# Sheet1.net
KiCad netlist of a schematic drawn in Altium Designer
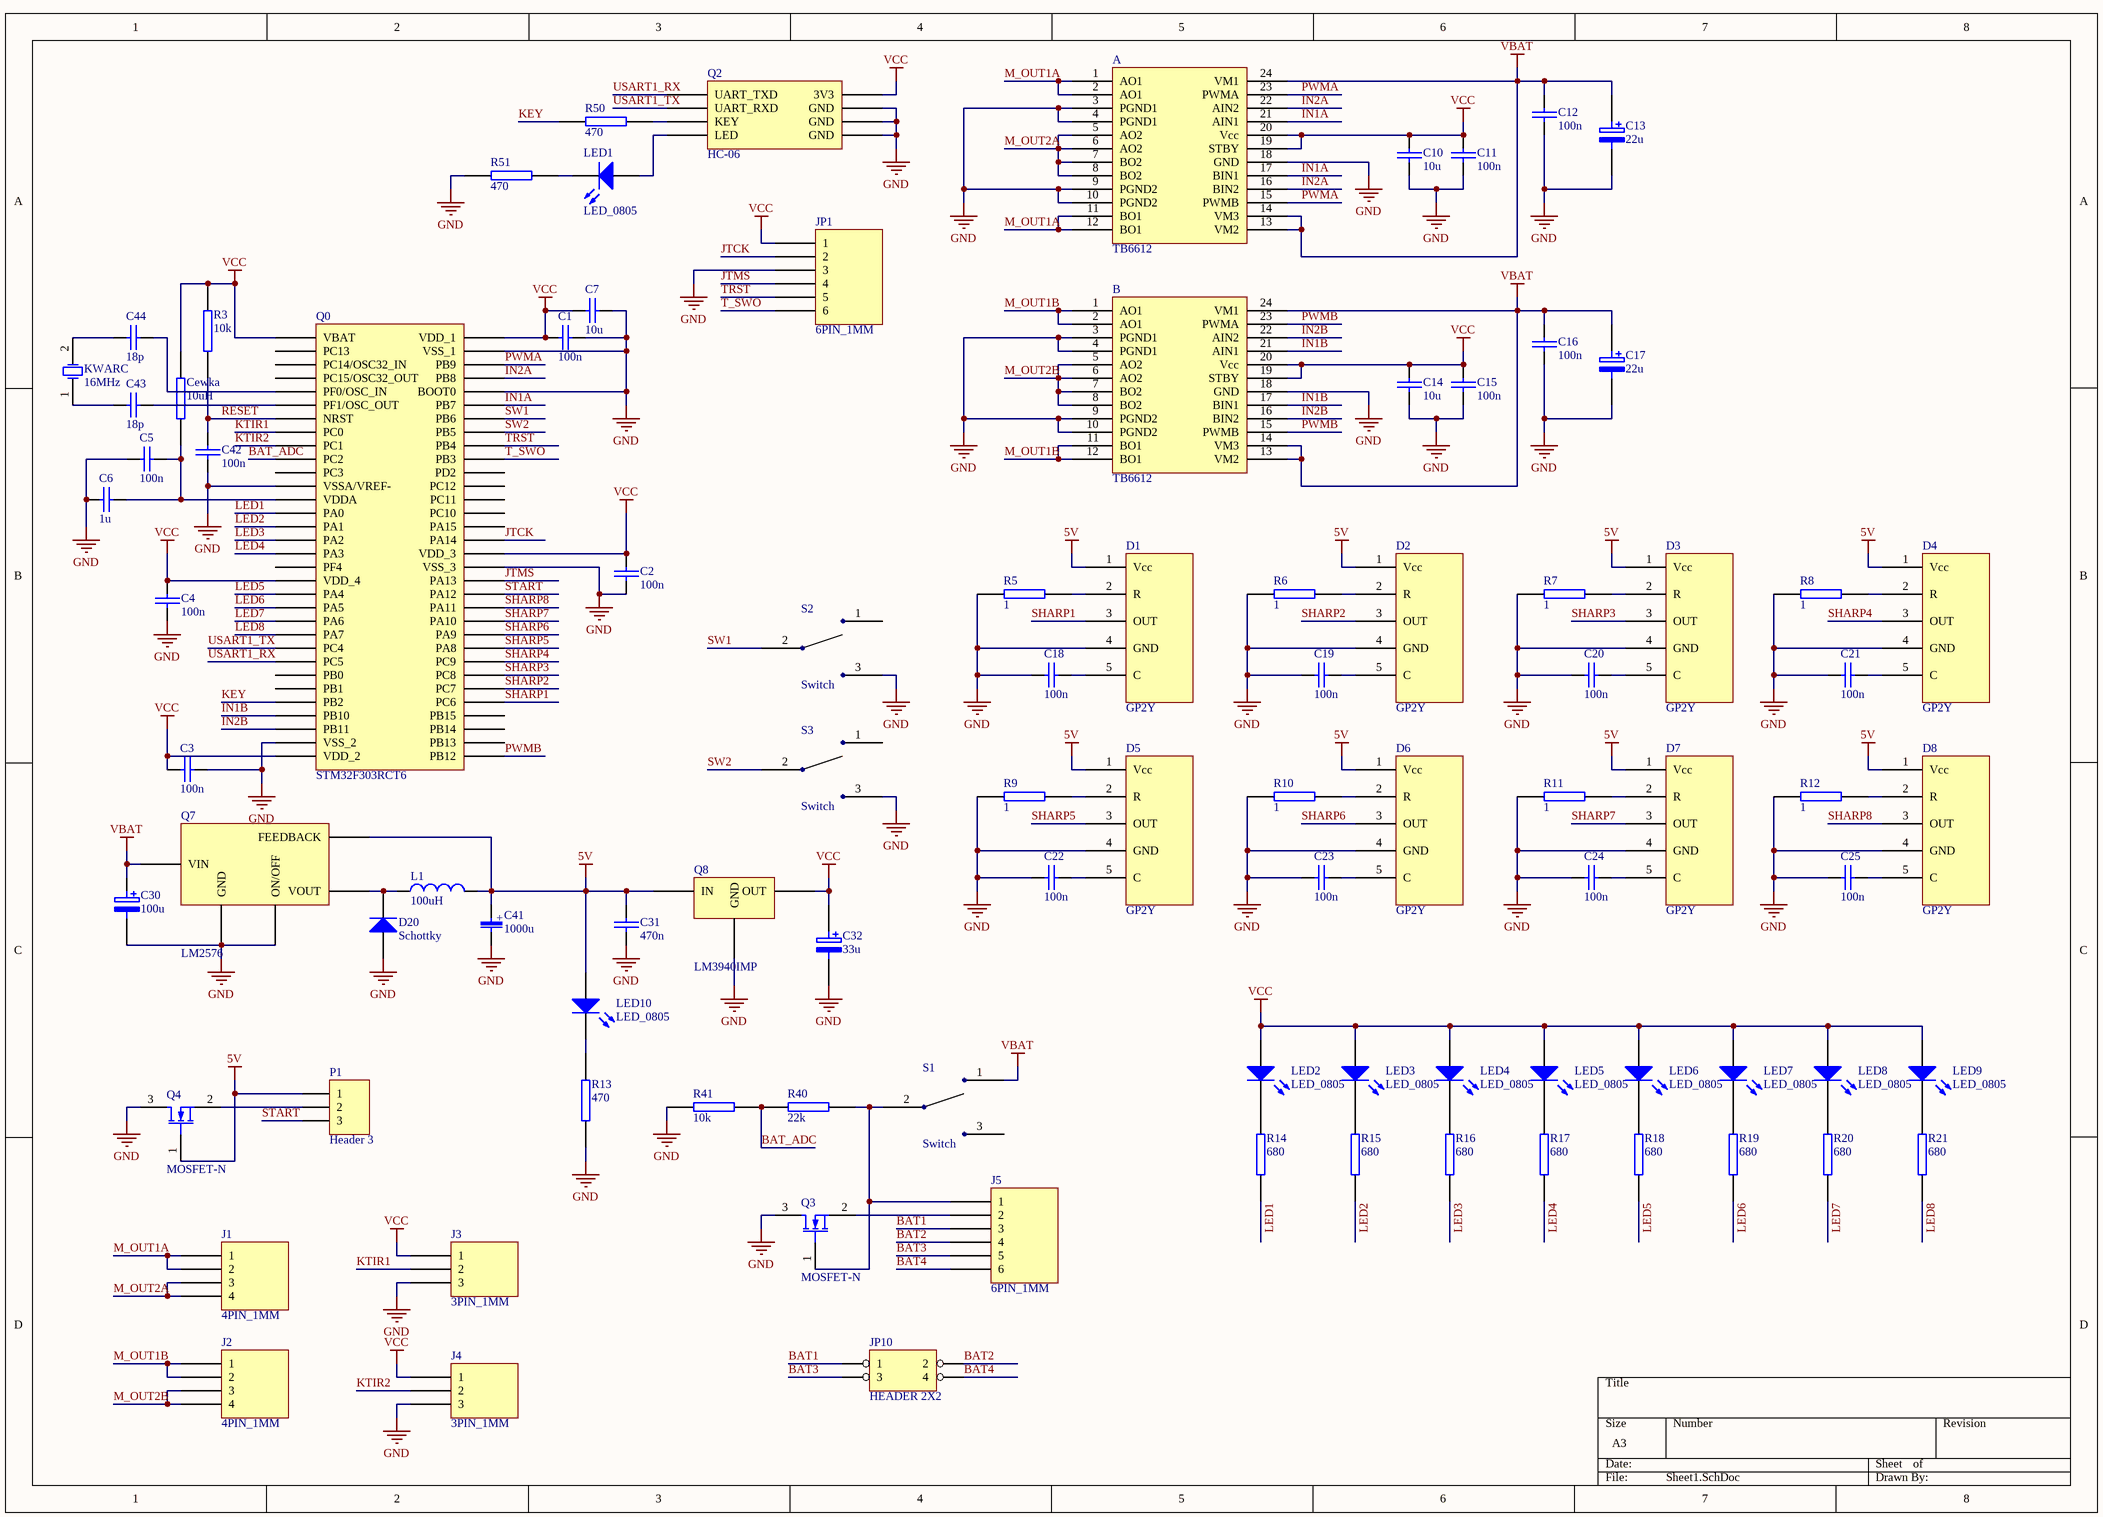
[diagram p0: Sheet1.SchDoc]

(export (version "E")
  (design (tool "Eeschema 10.0.6"))
  (components
    (comp (ref "A")
      (value "TB6612")
      (footprint "SSOP24")
      (libsource (lib "Integrated_Library1") (part "TB6612"))
    )
    (comp (ref "B")
      (value "TB6612")
      (footprint "SSOP24")
      (libsource (lib "Integrated_Library1") (part "TB6612"))
    )
    (comp (ref "C1")
      (value "100n")
      (footprint "0805 CAP")
      (description "Capacitor")
      (libsource (lib "Integrated_Library1") (part "CAP"))
    )
    (comp (ref "C2")
      (value "100n")
      (footprint "0805 CAP")
      (description "Capacitor")
      (libsource (lib "Integrated_Library1") (part "CAP"))
    )
    (comp (ref "C3")
      (value "100n")
      (footprint "0805 CAP")
      (description "Capacitor")
      (libsource (lib "Integrated_Library1") (part "CAP"))
    )
    (comp (ref "C4")
      (value "100n")
      (footprint "0805 CAP")
      (description "Capacitor")
      (libsource (lib "Integrated_Library1") (part "CAP"))
    )
    (comp (ref "C5")
      (value "100n")
      (footprint "0805 CAP")
      (description "Capacitor")
      (libsource (lib "Integrated_Library1") (part "CAP"))
    )
    (comp (ref "C6")
      (value "1u")
      (footprint "0805 CAP")
      (description "Capacitor")
      (libsource (lib "Integrated_Library1") (part "CAP"))
    )
    (comp (ref "C7")
      (value "10u")
      (footprint "0805 CAP")
      (description "Capacitor")
      (libsource (lib "Integrated_Library1") (part "CAP"))
    )
    (comp (ref "C10")
      (value "10u")
      (footprint "0805 CAP")
      (description "Capacitor")
      (libsource (lib "Integrated_Library1") (part "CAP"))
    )
    (comp (ref "C11")
      (value "100n")
      (footprint "0805 CAP")
      (description "Capacitor")
      (libsource (lib "Integrated_Library1") (part "CAP"))
    )
    (comp (ref "C12")
      (value "100n")
      (footprint "0805 CAP")
      (description "Capacitor")
      (libsource (lib "Integrated_Library1") (part "CAP"))
    )
    (comp (ref "C13") (value "22u") (footprint "TANTAL_A") (libsource (lib "Integrated_Library1") (part "E")))
    (comp (ref "C14")
      (value "10u")
      (footprint "0805 CAP")
      (description "Capacitor")
      (libsource (lib "Integrated_Library1") (part "CAP"))
    )
    (comp (ref "C15")
      (value "100n")
      (footprint "0805 CAP")
      (description "Capacitor")
      (libsource (lib "Integrated_Library1") (part "CAP"))
    )
    (comp (ref "C16")
      (value "100n")
      (footprint "0805 CAP")
      (description "Capacitor")
      (libsource (lib "Integrated_Library1") (part "CAP"))
    )
    (comp (ref "C17") (value "22u") (footprint "TANTAL_A") (libsource (lib "Integrated_Library1") (part "E")))
    (comp (ref "C18")
      (value "100n")
      (footprint "0805 CAP")
      (description "Capacitor")
      (libsource (lib "Integrated_Library1") (part "CAP"))
    )
    (comp (ref "C19")
      (value "100n")
      (footprint "0805 CAP")
      (description "Capacitor")
      (libsource (lib "Integrated_Library1") (part "CAP"))
    )
    (comp (ref "C20")
      (value "100n")
      (footprint "0805 CAP")
      (description "Capacitor")
      (libsource (lib "Integrated_Library1") (part "CAP"))
    )
    (comp (ref "C21")
      (value "100n")
      (footprint "0805 CAP")
      (description "Capacitor")
      (libsource (lib "Integrated_Library1") (part "CAP"))
    )
    (comp (ref "C22")
      (value "100n")
      (footprint "0805 CAP")
      (description "Capacitor")
      (libsource (lib "Integrated_Library1") (part "CAP"))
    )
    (comp (ref "C23")
      (value "100n")
      (footprint "0805 CAP")
      (description "Capacitor")
      (libsource (lib "Integrated_Library1") (part "CAP"))
    )
    (comp (ref "C24")
      (value "100n")
      (footprint "0805 CAP")
      (description "Capacitor")
      (libsource (lib "Integrated_Library1") (part "CAP"))
    )
    (comp (ref "C25")
      (value "100n")
      (footprint "0805 CAP")
      (description "Capacitor")
      (libsource (lib "Integrated_Library1") (part "CAP"))
    )
    (comp (ref "C30")
      (value "100u")
      (footprint "TANTAL_C")
      (description "Electrolytic Capacitor")
      (libsource (lib "Integrated_Library1") (part "ELECTRO2"))
    )
    (comp (ref "C31")
      (value "470n")
      (footprint "0805 CAP")
      (description "Capacitor")
      (libsource (lib "Integrated_Library1") (part "CAP"))
    )
    (comp (ref "C32")
      (value "33u")
      (footprint "TANTAL_C")
      (description "Electrolytic Capacitor")
      (libsource (lib "Integrated_Library1") (part "ELECTRO2"))
    )
    (comp (ref "C41")
      (value "1000u")
      (footprint "TANTAL_R")
      (libsource (lib "juziuLibrary") (part "TANTAL_R"))
    )
    (comp (ref "C42")
      (value "100n")
      (footprint "0805 CAP")
      (description "Capacitor")
      (libsource (lib "Integrated_Library1") (part "CAP"))
    )
    (comp (ref "C43")
      (value "18p")
      (footprint "0805 CAP")
      (description "Capacitor")
      (libsource (lib "Integrated_Library1") (part "CAP"))
    )
    (comp (ref "C44")
      (value "18p")
      (footprint "0805 CAP")
      (description "Capacitor")
      (libsource (lib "Integrated_Library1") (part "CAP"))
    )
    (comp (ref "Cewka")
      (value "10uH")
      (footprint "0805 RES")
      (libsource (lib "Integrated_Library1") (part "R"))
    )
    (comp (ref "D1")
      (value "GP2Y")
      (footprint "gp2y smd")
      (libsource (lib "Integrated_Library1") (part "GP2Y"))
    )
    (comp (ref "D2")
      (value "GP2Y")
      (footprint "gp2y smd")
      (libsource (lib "Integrated_Library1") (part "GP2Y"))
    )
    (comp (ref "D3")
      (value "GP2Y")
      (footprint "gp2y smd")
      (libsource (lib "Integrated_Library1") (part "GP2Y"))
    )
    (comp (ref "D4")
      (value "GP2Y")
      (footprint "gp2y smd")
      (libsource (lib "Integrated_Library1") (part "GP2Y"))
    )
    (comp (ref "D5")
      (value "GP2Y")
      (footprint "gp2y smd")
      (libsource (lib "Integrated_Library1") (part "GP2Y"))
    )
    (comp (ref "D6")
      (value "GP2Y")
      (footprint "gp2y smd")
      (libsource (lib "Integrated_Library1") (part "GP2Y"))
    )
    (comp (ref "D7")
      (value "GP2Y")
      (footprint "gp2y smd")
      (libsource (lib "Integrated_Library1") (part "GP2Y"))
    )
    (comp (ref "D8")
      (value "GP2Y")
      (footprint "gp2y smd")
      (libsource (lib "Integrated_Library1") (part "GP2Y"))
    )
    (comp (ref "D20") (value "Schottky") (footprint "SMB") (libsource (lib "juziuLibrary") (part "Schottky")))
    (comp (ref "J1")
      (value "4PIN_1MM")
      (footprint "CON_1mm_4pin")
      (libsource (lib "juziuLibrary") (part "CON_1MM_4PIN"))
    )
    (comp (ref "J2")
      (value "4PIN_1MM")
      (footprint "CON_1mm_4pin")
      (libsource (lib "juziuLibrary") (part "CON_1MM_4PIN"))
    )
    (comp (ref "J3")
      (value "3PIN_1MM")
      (footprint "CON_1MM_3PIN")
      (libsource (lib "juziuLibrary") (part "CON_1MM_3PIN"))
    )
    (comp (ref "J4")
      (value "3PIN_1MM")
      (footprint "CON_1MM_3PIN")
      (libsource (lib "juziuLibrary") (part "CON_1MM_3PIN"))
    )
    (comp (ref "J5")
      (value "6PIN_1MM")
      (footprint "CON_1MM_6PIN")
      (libsource (lib "juziuLibrary") (part "CON_1MM_6PIN"))
    )
    (comp (ref "JP1")
      (value "6PIN_1MM")
      (footprint "CON_1MM_6PIN")
      (libsource (lib "juziuLibrary") (part "CON_1MM_6PIN"))
    )
    (comp (ref "JP10")
      (value "HEADER 2X2")
      (footprint "MM2X2 SMD")
      (libsource (lib "Integrated_Library1") (part "HEADER 2X2"))
    )
    (comp (ref "KWARC")
      (value "16MHz")
      (footprint "16MHz")
      (description "Crystal Oscillator")
      (fields (field (name "PUBLISHER") "Altium Limited"))
      (libsource (lib "juziuLibrary") (part "XTAL"))
    )
    (comp (ref "L1") (value "100uH") (footprint "CEWKA") (libsource (lib "juziuLibrary") (part "CEWKA")))
    (comp (ref "LED1")
      (value "LED_0805")
      (footprint "0805")
      (libsource (lib "juziuLibrary") (part "LED_0805"))
    )
    (comp (ref "LED2")
      (value "LED_0805")
      (footprint "0805")
      (libsource (lib "juziuLibrary") (part "LED_0805"))
    )
    (comp (ref "LED3")
      (value "LED_0805")
      (footprint "0805")
      (libsource (lib "juziuLibrary") (part "LED_0805"))
    )
    (comp (ref "LED4")
      (value "LED_0805")
      (footprint "0805")
      (libsource (lib "juziuLibrary") (part "LED_0805"))
    )
    (comp (ref "LED5")
      (value "LED_0805")
      (footprint "0805")
      (libsource (lib "juziuLibrary") (part "LED_0805"))
    )
    (comp (ref "LED6")
      (value "LED_0805")
      (footprint "0805")
      (libsource (lib "juziuLibrary") (part "LED_0805"))
    )
    (comp (ref "LED7")
      (value "LED_0805")
      (footprint "0805")
      (libsource (lib "juziuLibrary") (part "LED_0805"))
    )
    (comp (ref "LED8")
      (value "LED_0805")
      (footprint "0805")
      (libsource (lib "juziuLibrary") (part "LED_0805"))
    )
    (comp (ref "LED9")
      (value "LED_0805")
      (footprint "0805")
      (libsource (lib "juziuLibrary") (part "LED_0805"))
    )
    (comp (ref "LED10")
      (value "LED_0805")
      (footprint "0805")
      (libsource (lib "juziuLibrary") (part "LED_0805"))
    )
    (comp (ref "P1")
      (value "Header 3")
      (footprint "HDR1X3")
      (description "Header, 3-Pin")
      (fields (field (name "PUBLISHER") "Altium Limited"))
      (libsource (lib "Miscellaneous Connectors") (part "Header 3"))
    )
    (comp (ref "Q0")
      (value "STM32F303RCT6")
      (footprint "STM32F303RCT6")
      (libsource (lib "STM32F303TRCT6") (part "STM32F303RCT6"))
    )
    (comp (ref "Q2")
      (value "HC-06")
      (footprint "PCBComponent_1")
      (description "Bluetooth")
      (libsource (lib "juziuLibrary") (part "Component_1"))
    )
    (comp (ref "Q3")
      (value "MOSFET-N")
      (footprint "N-MOSFET")
      (libsource (lib "juziuLibrary") (part "N-MOSFET"))
    )
    (comp (ref "Q4")
      (value "MOSFET-N")
      (footprint "N-MOSFET")
      (libsource (lib "juziuLibrary") (part "N-MOSFET"))
    )
    (comp (ref "Q7") (value "LM2576") (footprint "LM2576") (libsource (lib "juziuLibrary") (part "LM2576")))
    (comp (ref "Q8")
      (value "LM3940IMP")
      (footprint "LM3940IMP")
      (libsource (lib "juziuLibrary") (part "LM3940IMP"))
    )
    (comp (ref "R3") (value "10k") (footprint "0805 RES") (libsource (lib "Integrated_Library1") (part "R")))
    (comp (ref "R5") (value "1") (footprint "0805 RES") (libsource (lib "Integrated_Library1") (part "R")))
    (comp (ref "R6") (value "1") (footprint "0805 RES") (libsource (lib "Integrated_Library1") (part "R")))
    (comp (ref "R7") (value "1") (footprint "0805 RES") (libsource (lib "Integrated_Library1") (part "R")))
    (comp (ref "R8") (value "1") (footprint "0805 RES") (libsource (lib "Integrated_Library1") (part "R")))
    (comp (ref "R9") (value "1") (footprint "0805 RES") (libsource (lib "Integrated_Library1") (part "R")))
    (comp (ref "R10") (value "1") (footprint "0805 RES") (libsource (lib "Integrated_Library1") (part "R")))
    (comp (ref "R11") (value "1") (footprint "0805 RES") (libsource (lib "Integrated_Library1") (part "R")))
    (comp (ref "R12") (value "1") (footprint "0805 RES") (libsource (lib "Integrated_Library1") (part "R")))
    (comp (ref "R13") (value "470") (footprint "0805 RES") (libsource (lib "Integrated_Library1") (part "R")))
    (comp (ref "R14") (value "680") (footprint "0805 RES") (libsource (lib "Integrated_Library1") (part "R")))
    (comp (ref "R15") (value "680") (footprint "0805 RES") (libsource (lib "Integrated_Library1") (part "R")))
    (comp (ref "R16") (value "680") (footprint "0805 RES") (libsource (lib "Integrated_Library1") (part "R")))
    (comp (ref "R17") (value "680") (footprint "0805 RES") (libsource (lib "Integrated_Library1") (part "R")))
    (comp (ref "R18") (value "680") (footprint "0805 RES") (libsource (lib "Integrated_Library1") (part "R")))
    (comp (ref "R19") (value "680") (footprint "0805 RES") (libsource (lib "Integrated_Library1") (part "R")))
    (comp (ref "R20") (value "680") (footprint "0805 RES") (libsource (lib "Integrated_Library1") (part "R")))
    (comp (ref "R21") (value "680") (footprint "0805 RES") (libsource (lib "Integrated_Library1") (part "R")))
    (comp (ref "R40") (value "22k") (footprint "0805 RES") (libsource (lib "Integrated_Library1") (part "R")))
    (comp (ref "R41") (value "10k") (footprint "0805 RES") (libsource (lib "Integrated_Library1") (part "R")))
    (comp (ref "R50") (value "470") (footprint "0805 RES") (libsource (lib "Integrated_Library1") (part "R")))
    (comp (ref "R51") (value "470") (footprint "0805 RES") (libsource (lib "Integrated_Library1") (part "R")))
    (comp (ref "S1") (value "Switch") (footprint "Switch") (libsource (lib "juziuLibrary") (part "Switch")))
    (comp (ref "S2") (value "Switch") (footprint "Switch") (libsource (lib "juziuLibrary") (part "Switch")))
    (comp (ref "S3") (value "Switch") (footprint "Switch") (libsource (lib "juziuLibrary") (part "Switch")))
  )
  (nets
    (net (code "1") (name "/BAT1") (class "Default")
      (node (ref "J5") (pin "3") (pinfunction "3_3") (pintype "passive"))
      (node (ref "JP10") (pin "1") (pinfunction "1_1") (pintype "passive"))
    )
    (net (code "2") (name "/BAT2") (class "Default")
      (node (ref "J5") (pin "4") (pinfunction "4_4") (pintype "passive"))
      (node (ref "JP10") (pin "2") (pinfunction "2_2") (pintype "passive"))
    )
    (net (code "3") (name "/BAT3") (class "Default")
      (node (ref "J5") (pin "5") (pinfunction "5_5") (pintype "passive"))
      (node (ref "JP10") (pin "3") (pinfunction "3_3") (pintype "passive"))
    )
    (net (code "4") (name "/BAT4") (class "Default")
      (node (ref "J5") (pin "6") (pinfunction "6_6") (pintype "passive"))
      (node (ref "JP10") (pin "4") (pinfunction "4_4") (pintype "passive"))
    )
    (net (code "5") (name "/BAT_ADC") (class "Default")
      (node (ref "Q0") (pin "10") (pinfunction "PC2_10") (pintype "passive"))
      (node (ref "R40") (pin "2") (pinfunction "2_2") (pintype "passive"))
      (node (ref "R41") (pin "1") (pinfunction "1_1") (pintype "passive"))
    )
    (net (code "6") (name "/IN1A") (class "Default")
      (node (ref "A") (pin "17") (pinfunction "BIN1_17") (pintype "passive"))
      (node (ref "A") (pin "21") (pinfunction "AIN1_21") (pintype "passive"))
      (node (ref "Q0") (pin "59") (pinfunction "PB7_59") (pintype "passive"))
    )
    (net (code "7") (name "/IN1B") (class "Default")
      (node (ref "B") (pin "17") (pinfunction "BIN1_17") (pintype "passive"))
      (node (ref "B") (pin "21") (pinfunction "AIN1_21") (pintype "passive"))
      (node (ref "Q0") (pin "29") (pinfunction "PB10_29") (pintype "passive"))
    )
    (net (code "8") (name "/IN2A") (class "Default")
      (node (ref "A") (pin "16") (pinfunction "BIN2_16") (pintype "passive"))
      (node (ref "A") (pin "22") (pinfunction "AIN2_22") (pintype "passive"))
      (node (ref "Q0") (pin "61") (pinfunction "PB8_61") (pintype "passive"))
    )
    (net (code "9") (name "/IN2B") (class "Default")
      (node (ref "B") (pin "16") (pinfunction "BIN2_16") (pintype "passive"))
      (node (ref "B") (pin "22") (pinfunction "AIN2_22") (pintype "passive"))
      (node (ref "Q0") (pin "30") (pinfunction "PB11_30") (pintype "passive"))
    )
    (net (code "10") (name "/JTCK") (class "Default")
      (node (ref "JP1") (pin "2") (pinfunction "2_2") (pintype "passive"))
      (node (ref "Q0") (pin "49") (pinfunction "PA14_49") (pintype "passive"))
    )
    (net (code "11") (name "/JTMS") (class "Default")
      (node (ref "JP1") (pin "4") (pinfunction "4_4") (pintype "passive"))
      (node (ref "Q0") (pin "46") (pinfunction "PA13_46") (pintype "passive"))
    )
    (net (code "12") (name "/KEY") (class "Default")
      (node (ref "Q0") (pin "28") (pinfunction "PB2_28") (pintype "passive"))
      (node (ref "R50") (pin "1") (pinfunction "1_1") (pintype "passive"))
    )
    (net (code "13") (name "/KTIR1") (class "Default")
      (node (ref "J3") (pin "2") (pinfunction "2_2") (pintype "passive"))
      (node (ref "Q0") (pin "8") (pinfunction "PC0_8") (pintype "passive"))
    )
    (net (code "14") (name "/KTIR2") (class "Default")
      (node (ref "J4") (pin "2") (pinfunction "2_2") (pintype "passive"))
      (node (ref "Q0") (pin "9") (pinfunction "PC1_9") (pintype "passive"))
    )
    (net (code "15") (name "/LED1") (class "Default")
      (node (ref "Q0") (pin "14") (pinfunction "PA0_14") (pintype "passive"))
      (node (ref "R14") (pin "1") (pinfunction "1_1") (pintype "passive"))
    )
    (net (code "16") (name "/LED2") (class "Default")
      (node (ref "Q0") (pin "15") (pinfunction "PA1_15") (pintype "passive"))
      (node (ref "R15") (pin "1") (pinfunction "1_1") (pintype "passive"))
    )
    (net (code "17") (name "/LED3") (class "Default")
      (node (ref "Q0") (pin "16") (pinfunction "PA2_16") (pintype "passive"))
      (node (ref "R16") (pin "1") (pinfunction "1_1") (pintype "passive"))
    )
    (net (code "18") (name "/LED4") (class "Default")
      (node (ref "Q0") (pin "17") (pinfunction "PA3_17") (pintype "passive"))
      (node (ref "R17") (pin "1") (pinfunction "1_1") (pintype "passive"))
    )
    (net (code "19") (name "/LED5") (class "Default")
      (node (ref "Q0") (pin "20") (pinfunction "PA4_20") (pintype "passive"))
      (node (ref "R18") (pin "1") (pinfunction "1_1") (pintype "passive"))
    )
    (net (code "20") (name "/LED6") (class "Default")
      (node (ref "Q0") (pin "21") (pinfunction "PA5_21") (pintype "passive"))
      (node (ref "R19") (pin "1") (pinfunction "1_1") (pintype "passive"))
    )
    (net (code "21") (name "/LED7") (class "Default")
      (node (ref "Q0") (pin "22") (pinfunction "PA6_22") (pintype "passive"))
      (node (ref "R20") (pin "1") (pinfunction "1_1") (pintype "passive"))
    )
    (net (code "22") (name "/LED8") (class "Default")
      (node (ref "Q0") (pin "23") (pinfunction "PA7_23") (pintype "passive"))
      (node (ref "R21") (pin "1") (pinfunction "1_1") (pintype "passive"))
    )
    (net (code "23") (name "/M_OUT1A") (class "Default")
      (node (ref "A") (pin "1") (pinfunction "AO1_1") (pintype "passive"))
      (node (ref "A") (pin "11") (pinfunction "BO1_11") (pintype "passive"))
      (node (ref "A") (pin "12") (pinfunction "BO1_12") (pintype "passive"))
      (node (ref "A") (pin "2") (pinfunction "AO1_2") (pintype "passive"))
      (node (ref "J1") (pin "1") (pinfunction "1_1") (pintype "passive"))
      (node (ref "J1") (pin "2") (pinfunction "2_2") (pintype "passive"))
    )
    (net (code "24") (name "/M_OUT1B") (class "Default")
      (node (ref "B") (pin "1") (pinfunction "AO1_1") (pintype "passive"))
      (node (ref "B") (pin "11") (pinfunction "BO1_11") (pintype "passive"))
      (node (ref "B") (pin "12") (pinfunction "BO1_12") (pintype "passive"))
      (node (ref "B") (pin "2") (pinfunction "AO1_2") (pintype "passive"))
      (node (ref "J2") (pin "1") (pinfunction "1_1") (pintype "passive"))
      (node (ref "J2") (pin "2") (pinfunction "2_2") (pintype "passive"))
    )
    (net (code "25") (name "/M_OUT2A") (class "Default")
      (node (ref "A") (pin "5") (pinfunction "AO2_5") (pintype "passive"))
      (node (ref "A") (pin "6") (pinfunction "AO2_6") (pintype "passive"))
      (node (ref "A") (pin "7") (pinfunction "BO2_7") (pintype "passive"))
      (node (ref "A") (pin "8") (pinfunction "BO2_8") (pintype "passive"))
      (node (ref "J1") (pin "3") (pinfunction "3_3") (pintype "passive"))
      (node (ref "J1") (pin "4") (pinfunction "4_4") (pintype "passive"))
    )
    (net (code "26") (name "/M_OUT2B") (class "Default")
      (node (ref "B") (pin "5") (pinfunction "AO2_5") (pintype "passive"))
      (node (ref "B") (pin "6") (pinfunction "AO2_6") (pintype "passive"))
      (node (ref "B") (pin "7") (pinfunction "BO2_7") (pintype "passive"))
      (node (ref "B") (pin "8") (pinfunction "BO2_8") (pintype "passive"))
      (node (ref "J2") (pin "3") (pinfunction "3_3") (pintype "passive"))
      (node (ref "J2") (pin "4") (pinfunction "4_4") (pintype "passive"))
    )
    (net (code "27") (name "/PWMA") (class "Default")
      (node (ref "A") (pin "15") (pinfunction "PWMB_15") (pintype "passive"))
      (node (ref "A") (pin "23") (pinfunction "PWMA_23") (pintype "passive"))
      (node (ref "Q0") (pin "62") (pinfunction "PB9_62") (pintype "passive"))
    )
    (net (code "28") (name "/PWMB") (class "Default")
      (node (ref "B") (pin "15") (pinfunction "PWMB_15") (pintype "passive"))
      (node (ref "B") (pin "23") (pinfunction "PWMA_23") (pintype "passive"))
      (node (ref "Q0") (pin "33") (pinfunction "PB12_33") (pintype "passive"))
    )
    (net (code "29") (name "/RESET") (class "Default")
      (node (ref "C42") (pin "1") (pinfunction "1_1") (pintype "passive"))
      (node (ref "Q0") (pin "7") (pinfunction "NRST_7") (pintype "passive"))
      (node (ref "R3") (pin "1") (pinfunction "1_1") (pintype "passive"))
    )
    (net (code "30") (name "/SHARP1") (class "Default")
      (node (ref "D1") (pin "3") (pinfunction "OUT_3") (pintype "passive"))
      (node (ref "Q0") (pin "37") (pinfunction "PC6_37") (pintype "passive"))
    )
    (net (code "31") (name "/SHARP2") (class "Default")
      (node (ref "D2") (pin "3") (pinfunction "OUT_3") (pintype "passive"))
      (node (ref "Q0") (pin "38") (pinfunction "PC7_38") (pintype "passive"))
    )
    (net (code "32") (name "/SHARP3") (class "Default")
      (node (ref "D3") (pin "3") (pinfunction "OUT_3") (pintype "passive"))
      (node (ref "Q0") (pin "39") (pinfunction "PC8_39") (pintype "passive"))
    )
    (net (code "33") (name "/SHARP4") (class "Default")
      (node (ref "D4") (pin "3") (pinfunction "OUT_3") (pintype "passive"))
      (node (ref "Q0") (pin "40") (pinfunction "PC9_40") (pintype "passive"))
    )
    (net (code "34") (name "/SHARP5") (class "Default")
      (node (ref "D5") (pin "3") (pinfunction "OUT_3") (pintype "passive"))
      (node (ref "Q0") (pin "41") (pinfunction "PA8_41") (pintype "passive"))
    )
    (net (code "35") (name "/SHARP6") (class "Default")
      (node (ref "D6") (pin "3") (pinfunction "OUT_3") (pintype "passive"))
      (node (ref "Q0") (pin "42") (pinfunction "PA9_42") (pintype "passive"))
    )
    (net (code "36") (name "/SHARP7") (class "Default")
      (node (ref "D7") (pin "3") (pinfunction "OUT_3") (pintype "passive"))
      (node (ref "Q0") (pin "43") (pinfunction "PA10_43") (pintype "passive"))
    )
    (net (code "37") (name "/SHARP8") (class "Default")
      (node (ref "D8") (pin "3") (pinfunction "OUT_3") (pintype "passive"))
      (node (ref "Q0") (pin "44") (pinfunction "PA11_44") (pintype "passive"))
    )
    (net (code "38") (name "/START") (class "Default")
      (node (ref "P1") (pin "3") (pinfunction "3_3") (pintype "passive"))
      (node (ref "Q0") (pin "45") (pinfunction "PA12_45") (pintype "passive"))
    )
    (net (code "39") (name "/SW1") (class "Default")
      (node (ref "Q0") (pin "58") (pinfunction "PB6_58") (pintype "passive"))
      (node (ref "S2") (pin "2") (pintype "passive"))
    )
    (net (code "40") (name "/SW2") (class "Default")
      (node (ref "Q0") (pin "57") (pinfunction "PB5_57") (pintype "passive"))
      (node (ref "S3") (pin "2") (pintype "passive"))
    )
    (net (code "41") (name "/TRST") (class "Default")
      (node (ref "JP1") (pin "5") (pinfunction "5_5") (pintype "passive"))
      (node (ref "Q0") (pin "56") (pinfunction "PB4_56") (pintype "passive"))
    )
    (net (code "42") (name "/T_SWO") (class "Default")
      (node (ref "JP1") (pin "6") (pinfunction "6_6") (pintype "passive"))
      (node (ref "Q0") (pin "55") (pinfunction "PB3_55") (pintype "passive"))
    )
    (net (code "43") (name "/USART1_RX") (class "Default")
      (node (ref "Q0") (pin "25") (pinfunction "PC5_25") (pintype "passive"))
      (node (ref "Q2") (pin "1") (pinfunction "UART_TXD_1") (pintype "passive"))
    )
    (net (code "44") (name "/USART1_TX") (class "Default")
      (node (ref "Q0") (pin "24") (pinfunction "PC4_24") (pintype "passive"))
      (node (ref "Q2") (pin "2") (pinfunction "UART_RXD_2") (pintype "passive"))
    )
    (net (code "45") (name "5V") (class "Default")
      (node (ref "C31") (pin "2") (pinfunction "2_2") (pintype "passive"))
      (node (ref "C41") (pin "1") (pinfunction "1_1") (pintype "passive"))
      (node (ref "D1") (pin "1") (pinfunction "Vcc_1") (pintype "passive"))
      (node (ref "D2") (pin "1") (pinfunction "Vcc_1") (pintype "passive"))
      (node (ref "D3") (pin "1") (pinfunction "Vcc_1") (pintype "passive"))
      (node (ref "D4") (pin "1") (pinfunction "Vcc_1") (pintype "passive"))
      (node (ref "D5") (pin "1") (pinfunction "Vcc_1") (pintype "passive"))
      (node (ref "D6") (pin "1") (pinfunction "Vcc_1") (pintype "passive"))
      (node (ref "D7") (pin "1") (pinfunction "Vcc_1") (pintype "passive"))
      (node (ref "D8") (pin "1") (pinfunction "Vcc_1") (pintype "passive"))
      (node (ref "L1") (pin "2") (pinfunction "2_2") (pintype "passive"))
      (node (ref "LED10") (pin "2") (pinfunction "A_2") (pintype "passive"))
      (node (ref "P1") (pin "1") (pinfunction "1_1") (pintype "passive"))
      (node (ref "Q4") (pin "1") (pinfunction "G_1") (pintype "passive"))
      (node (ref "Q7") (pin "4") (pinfunction "FEEDBACK_4") (pintype "passive"))
      (node (ref "Q8") (pin "IN") (pinfunction "IN_IN") (pintype "passive"))
    )
    (net (code "46") (name "GND") (class "Default")
      (node (ref "A") (pin "10") (pinfunction "PGND2_10") (pintype "passive"))
      (node (ref "A") (pin "18") (pinfunction "GND_18") (pintype "passive"))
      (node (ref "A") (pin "3") (pinfunction "PGND1_3") (pintype "passive"))
      (node (ref "A") (pin "4") (pinfunction "PGND1_4") (pintype "passive"))
      (node (ref "A") (pin "9") (pinfunction "PGND2_9") (pintype "passive"))
      (node (ref "B") (pin "10") (pinfunction "PGND2_10") (pintype "passive"))
      (node (ref "B") (pin "18") (pinfunction "GND_18") (pintype "passive"))
      (node (ref "B") (pin "3") (pinfunction "PGND1_3") (pintype "passive"))
      (node (ref "B") (pin "4") (pinfunction "PGND1_4") (pintype "passive"))
      (node (ref "B") (pin "9") (pinfunction "PGND2_9") (pintype "passive"))
      (node (ref "C1") (pin "2") (pinfunction "2_2") (pintype "passive"))
      (node (ref "C10") (pin "2") (pinfunction "2_2") (pintype "passive"))
      (node (ref "C11") (pin "2") (pinfunction "2_2") (pintype "passive"))
      (node (ref "C12") (pin "2") (pinfunction "2_2") (pintype "passive"))
      (node (ref "C13") (pin "2") (pinfunction "2_2") (pintype "passive"))
      (node (ref "C14") (pin "2") (pinfunction "2_2") (pintype "passive"))
      (node (ref "C15") (pin "2") (pinfunction "2_2") (pintype "passive"))
      (node (ref "C16") (pin "2") (pinfunction "2_2") (pintype "passive"))
      (node (ref "C17") (pin "2") (pinfunction "2_2") (pintype "passive"))
      (node (ref "C18") (pin "1") (pinfunction "1_1") (pintype "passive"))
      (node (ref "C19") (pin "1") (pinfunction "1_1") (pintype "passive"))
      (node (ref "C2") (pin "2") (pinfunction "2_2") (pintype "passive"))
      (node (ref "C20") (pin "1") (pinfunction "1_1") (pintype "passive"))
      (node (ref "C21") (pin "1") (pinfunction "1_1") (pintype "passive"))
      (node (ref "C22") (pin "1") (pinfunction "1_1") (pintype "passive"))
      (node (ref "C23") (pin "1") (pinfunction "1_1") (pintype "passive"))
      (node (ref "C24") (pin "1") (pinfunction "1_1") (pintype "passive"))
      (node (ref "C25") (pin "1") (pinfunction "1_1") (pintype "passive"))
      (node (ref "C3") (pin "2") (pinfunction "2_2") (pintype "passive"))
      (node (ref "C30") (pin "2") (pinfunction "2_2") (pintype "passive"))
      (node (ref "C31") (pin "1") (pinfunction "1_1") (pintype "passive"))
      (node (ref "C32") (pin "2") (pinfunction "2_2") (pintype "passive"))
      (node (ref "C4") (pin "2") (pinfunction "2_2") (pintype "passive"))
      (node (ref "C41") (pin "2") (pinfunction "2_2") (pintype "passive"))
      (node (ref "C42") (pin "2") (pinfunction "2_2") (pintype "passive"))
      (node (ref "C5") (pin "2") (pinfunction "2_2") (pintype "passive"))
      (node (ref "C6") (pin "1") (pinfunction "1_1") (pintype "passive"))
      (node (ref "C7") (pin "2") (pinfunction "2_2") (pintype "passive"))
      (node (ref "D1") (pin "4") (pinfunction "GND_4") (pintype "passive"))
      (node (ref "D2") (pin "4") (pinfunction "GND_4") (pintype "passive"))
      (node (ref "D20") (pin "1") (pinfunction "A_1") (pintype "passive"))
      (node (ref "D3") (pin "4") (pinfunction "GND_4") (pintype "passive"))
      (node (ref "D4") (pin "4") (pinfunction "GND_4") (pintype "passive"))
      (node (ref "D5") (pin "4") (pinfunction "GND_4") (pintype "passive"))
      (node (ref "D6") (pin "4") (pinfunction "GND_4") (pintype "passive"))
      (node (ref "D7") (pin "4") (pinfunction "GND_4") (pintype "passive"))
      (node (ref "D8") (pin "4") (pinfunction "GND_4") (pintype "passive"))
      (node (ref "J3") (pin "3") (pinfunction "3_3") (pintype "passive"))
      (node (ref "J4") (pin "3") (pinfunction "3_3") (pintype "passive"))
      (node (ref "JP1") (pin "3") (pinfunction "3_3") (pintype "passive"))
      (node (ref "Q0") (pin "12") (pinfunction "VSSA/VREF-_12") (pintype "passive"))
      (node (ref "Q0") (pin "31") (pinfunction "VSS_2_31") (pintype "passive"))
      (node (ref "Q0") (pin "47") (pinfunction "VSS_3_47") (pintype "passive"))
      (node (ref "Q0") (pin "60") (pinfunction "BOOT0_60") (pintype "passive"))
      (node (ref "Q0") (pin "63") (pinfunction "VSS_1_63") (pintype "passive"))
      (node (ref "Q2") (pin "4") (pinfunction "GND_4") (pintype "passive"))
      (node (ref "Q2") (pin "5") (pinfunction "GND_5") (pintype "passive"))
      (node (ref "Q2") (pin "6") (pinfunction "GND_6") (pintype "passive"))
      (node (ref "Q3") (pin "3") (pinfunction "D_3") (pintype "passive"))
      (node (ref "Q4") (pin "3") (pinfunction "D_3") (pintype "passive"))
      (node (ref "Q7") (pin "3") (pinfunction "GND_3") (pintype "passive"))
      (node (ref "Q7") (pin "5") (pinfunction "ON/OFF_5") (pintype "passive"))
      (node (ref "Q8") (pin "GND") (pinfunction "GND_GND") (pintype "passive"))
      (node (ref "R10") (pin "1") (pinfunction "1_1") (pintype "passive"))
      (node (ref "R11") (pin "1") (pinfunction "1_1") (pintype "passive"))
      (node (ref "R12") (pin "1") (pinfunction "1_1") (pintype "passive"))
      (node (ref "R13") (pin "1") (pinfunction "1_1") (pintype "passive"))
      (node (ref "R41") (pin "2") (pinfunction "2_2") (pintype "passive"))
      (node (ref "R5") (pin "1") (pinfunction "1_1") (pintype "passive"))
      (node (ref "R51") (pin "1") (pinfunction "1_1") (pintype "passive"))
      (node (ref "R6") (pin "1") (pinfunction "1_1") (pintype "passive"))
      (node (ref "R7") (pin "1") (pinfunction "1_1") (pintype "passive"))
      (node (ref "R8") (pin "1") (pinfunction "1_1") (pintype "passive"))
      (node (ref "R9") (pin "1") (pinfunction "1_1") (pintype "passive"))
      (node (ref "S2") (pin "3") (pintype "passive"))
      (node (ref "S3") (pin "3") (pintype "passive"))
    )
    (net (code "47") (name "Net-(D1-C)") (class "Default")
      (node (ref "C18") (pin "2") (pinfunction "2_2") (pintype "passive"))
      (node (ref "D1") (pin "5") (pinfunction "C_5") (pintype "passive"))
    )
    (net (code "48") (name "Net-(D1-R)") (class "Default")
      (node (ref "D1") (pin "2") (pinfunction "R_2") (pintype "passive"))
      (node (ref "R5") (pin "2") (pinfunction "2_2") (pintype "passive"))
    )
    (net (code "49") (name "Net-(D2-C)") (class "Default")
      (node (ref "C19") (pin "2") (pinfunction "2_2") (pintype "passive"))
      (node (ref "D2") (pin "5") (pinfunction "C_5") (pintype "passive"))
    )
    (net (code "50") (name "Net-(D2-R)") (class "Default")
      (node (ref "D2") (pin "2") (pinfunction "R_2") (pintype "passive"))
      (node (ref "R6") (pin "2") (pinfunction "2_2") (pintype "passive"))
    )
    (net (code "51") (name "Net-(D3-C)") (class "Default")
      (node (ref "C20") (pin "2") (pinfunction "2_2") (pintype "passive"))
      (node (ref "D3") (pin "5") (pinfunction "C_5") (pintype "passive"))
    )
    (net (code "52") (name "Net-(D3-R)") (class "Default")
      (node (ref "D3") (pin "2") (pinfunction "R_2") (pintype "passive"))
      (node (ref "R7") (pin "2") (pinfunction "2_2") (pintype "passive"))
    )
    (net (code "53") (name "Net-(D4-C)") (class "Default")
      (node (ref "C21") (pin "2") (pinfunction "2_2") (pintype "passive"))
      (node (ref "D4") (pin "5") (pinfunction "C_5") (pintype "passive"))
    )
    (net (code "54") (name "Net-(D4-R)") (class "Default")
      (node (ref "D4") (pin "2") (pinfunction "R_2") (pintype "passive"))
      (node (ref "R8") (pin "2") (pinfunction "2_2") (pintype "passive"))
    )
    (net (code "55") (name "Net-(D5-C)") (class "Default")
      (node (ref "C22") (pin "2") (pinfunction "2_2") (pintype "passive"))
      (node (ref "D5") (pin "5") (pinfunction "C_5") (pintype "passive"))
    )
    (net (code "56") (name "Net-(D5-R)") (class "Default")
      (node (ref "D5") (pin "2") (pinfunction "R_2") (pintype "passive"))
      (node (ref "R9") (pin "2") (pinfunction "2_2") (pintype "passive"))
    )
    (net (code "57") (name "Net-(D6-C)") (class "Default")
      (node (ref "C23") (pin "2") (pinfunction "2_2") (pintype "passive"))
      (node (ref "D6") (pin "5") (pinfunction "C_5") (pintype "passive"))
    )
    (net (code "58") (name "Net-(D6-R)") (class "Default")
      (node (ref "D6") (pin "2") (pinfunction "R_2") (pintype "passive"))
      (node (ref "R10") (pin "2") (pinfunction "2_2") (pintype "passive"))
    )
    (net (code "59") (name "Net-(D7-C)") (class "Default")
      (node (ref "C24") (pin "2") (pinfunction "2_2") (pintype "passive"))
      (node (ref "D7") (pin "5") (pinfunction "C_5") (pintype "passive"))
    )
    (net (code "60") (name "Net-(D7-R)") (class "Default")
      (node (ref "D7") (pin "2") (pinfunction "R_2") (pintype "passive"))
      (node (ref "R11") (pin "2") (pinfunction "2_2") (pintype "passive"))
    )
    (net (code "61") (name "Net-(D8-C)") (class "Default")
      (node (ref "C25") (pin "2") (pinfunction "2_2") (pintype "passive"))
      (node (ref "D8") (pin "5") (pinfunction "C_5") (pintype "passive"))
    )
    (net (code "62") (name "Net-(D8-R)") (class "Default")
      (node (ref "D8") (pin "2") (pinfunction "R_2") (pintype "passive"))
      (node (ref "R12") (pin "2") (pinfunction "2_2") (pintype "passive"))
    )
    (net (code "63") (name "Net-(D20-K)") (class "Default")
      (node (ref "D20") (pin "2") (pinfunction "K_2") (pintype "passive"))
      (node (ref "L1") (pin "1") (pinfunction "1_1") (pintype "passive"))
      (node (ref "Q7") (pin "2") (pinfunction "VOUT_2") (pintype "passive"))
    )
    (net (code "64") (name "Net-(KWARC-OSC1)") (class "Default")
      (node (ref "C43") (pin "1") (pinfunction "1_1") (pintype "passive"))
      (node (ref "KWARC") (pin "1") (pinfunction "OSC1_1") (pintype "passive"))
    )
    (net (code "65") (name "Net-(KWARC-OSC2)") (class "Default")
      (node (ref "C44") (pin "1") (pinfunction "1_1") (pintype "passive"))
      (node (ref "KWARC") (pin "2") (pinfunction "OSC2_2") (pintype "passive"))
    )
    (net (code "66") (name "Net-(LED1-A)") (class "Default")
      (node (ref "LED1") (pin "2") (pinfunction "A_2") (pintype "passive"))
      (node (ref "Q2") (pin "7") (pinfunction "LED_7") (pintype "passive"))
    )
    (net (code "67") (name "Net-(LED1-K)") (class "Default")
      (node (ref "LED1") (pin "1") (pinfunction "K_1") (pintype "passive"))
      (node (ref "R51") (pin "2") (pinfunction "2_2") (pintype "passive"))
    )
    (net (code "68") (name "Net-(LED2-K)") (class "Default")
      (node (ref "LED2") (pin "1") (pinfunction "K_1") (pintype "passive"))
      (node (ref "R14") (pin "2") (pinfunction "2_2") (pintype "passive"))
    )
    (net (code "69") (name "Net-(LED3-K)") (class "Default")
      (node (ref "LED3") (pin "1") (pinfunction "K_1") (pintype "passive"))
      (node (ref "R15") (pin "2") (pinfunction "2_2") (pintype "passive"))
    )
    (net (code "70") (name "Net-(LED4-K)") (class "Default")
      (node (ref "LED4") (pin "1") (pinfunction "K_1") (pintype "passive"))
      (node (ref "R16") (pin "2") (pinfunction "2_2") (pintype "passive"))
    )
    (net (code "71") (name "Net-(LED5-K)") (class "Default")
      (node (ref "LED5") (pin "1") (pinfunction "K_1") (pintype "passive"))
      (node (ref "R17") (pin "2") (pinfunction "2_2") (pintype "passive"))
    )
    (net (code "72") (name "Net-(LED6-K)") (class "Default")
      (node (ref "LED6") (pin "1") (pinfunction "K_1") (pintype "passive"))
      (node (ref "R18") (pin "2") (pinfunction "2_2") (pintype "passive"))
    )
    (net (code "73") (name "Net-(LED7-K)") (class "Default")
      (node (ref "LED7") (pin "1") (pinfunction "K_1") (pintype "passive"))
      (node (ref "R19") (pin "2") (pinfunction "2_2") (pintype "passive"))
    )
    (net (code "74") (name "Net-(LED8-K)") (class "Default")
      (node (ref "LED8") (pin "1") (pinfunction "K_1") (pintype "passive"))
      (node (ref "R20") (pin "2") (pinfunction "2_2") (pintype "passive"))
    )
    (net (code "75") (name "Net-(LED9-K)") (class "Default")
      (node (ref "LED9") (pin "1") (pinfunction "K_1") (pintype "passive"))
      (node (ref "R21") (pin "2") (pinfunction "2_2") (pintype "passive"))
    )
    (net (code "76") (name "Net-(LED10-K)") (class "Default")
      (node (ref "LED10") (pin "1") (pinfunction "K_1") (pintype "passive"))
      (node (ref "R13") (pin "2") (pinfunction "2_2") (pintype "passive"))
    )
    (net (code "77") (name "Net-(Q0-PF0{slash}OSC_IN)") (class "Default")
      (node (ref "C44") (pin "2") (pinfunction "2_2") (pintype "passive"))
      (node (ref "Q0") (pin "5") (pinfunction "PF0/OSC_IN_5") (pintype "passive"))
    )
    (net (code "78") (name "Net-(Q0-PF1{slash}OSC_OUT)") (class "Default")
      (node (ref "C43") (pin "2") (pinfunction "2_2") (pintype "passive"))
      (node (ref "Q0") (pin "6") (pinfunction "PF1/OSC_OUT_6") (pintype "passive"))
    )
    (net (code "79") (name "Net-(Q0-VDDA)") (class "Default")
      (node (ref "C5") (pin "1") (pinfunction "1_1") (pintype "passive"))
      (node (ref "C6") (pin "2") (pinfunction "2_2") (pintype "passive"))
      (node (ref "Cewka") (pin "1") (pinfunction "1_1") (pintype "passive"))
      (node (ref "Q0") (pin "13") (pinfunction "VDDA_13") (pintype "passive"))
    )
    (net (code "80") (name "Net-(Q2-KEY)") (class "Default")
      (node (ref "Q2") (pin "8") (pinfunction "KEY_8") (pintype "passive"))
      (node (ref "R50") (pin "2") (pinfunction "2_2") (pintype "passive"))
    )
    (net (code "81") (name "Net-(Q3-G)") (class "Default")
      (node (ref "J5") (pin "1") (pinfunction "1_1") (pintype "passive"))
      (node (ref "Q3") (pin "1") (pinfunction "G_1") (pintype "passive"))
      (node (ref "R40") (pin "1") (pinfunction "1_1") (pintype "passive"))
      (node (ref "S1") (pin "2") (pintype "passive"))
    )
    (net (code "82") (name "Net-(Q3-S)") (class "Default")
      (node (ref "J5") (pin "2") (pinfunction "2_2") (pintype "passive"))
      (node (ref "Q3") (pin "2") (pinfunction "S_2") (pintype "passive"))
    )
    (net (code "83") (name "Net-(Q4-S)") (class "Default")
      (node (ref "P1") (pin "2") (pinfunction "2_2") (pintype "passive"))
      (node (ref "Q4") (pin "2") (pinfunction "S_2") (pintype "passive"))
    )
    (net (code "84") (name "VBAT") (class "Default")
      (node (ref "A") (pin "13") (pinfunction "VM2_13") (pintype "passive"))
      (node (ref "A") (pin "14") (pinfunction "VM3_14") (pintype "passive"))
      (node (ref "A") (pin "24") (pinfunction "VM1_24") (pintype "passive"))
      (node (ref "B") (pin "13") (pinfunction "VM2_13") (pintype "passive"))
      (node (ref "B") (pin "14") (pinfunction "VM3_14") (pintype "passive"))
      (node (ref "B") (pin "24") (pinfunction "VM1_24") (pintype "passive"))
      (node (ref "C12") (pin "1") (pinfunction "1_1") (pintype "passive"))
      (node (ref "C13") (pin "1") (pinfunction "1_1") (pintype "passive"))
      (node (ref "C16") (pin "1") (pinfunction "1_1") (pintype "passive"))
      (node (ref "C17") (pin "1") (pinfunction "1_1") (pintype "passive"))
      (node (ref "C30") (pin "1") (pinfunction "1_1") (pintype "passive"))
      (node (ref "Q7") (pin "1") (pinfunction "VIN_1") (pintype "passive"))
      (node (ref "S1") (pin "1") (pintype "passive"))
    )
    (net (code "85") (name "VCC") (class "Default")
      (node (ref "A") (pin "19") (pinfunction "STBY_19") (pintype "passive"))
      (node (ref "A") (pin "20") (pinfunction "Vcc_20") (pintype "passive"))
      (node (ref "B") (pin "19") (pinfunction "STBY_19") (pintype "passive"))
      (node (ref "B") (pin "20") (pinfunction "Vcc_20") (pintype "passive"))
      (node (ref "C1") (pin "1") (pinfunction "1_1") (pintype "passive"))
      (node (ref "C10") (pin "1") (pinfunction "1_1") (pintype "passive"))
      (node (ref "C11") (pin "1") (pinfunction "1_1") (pintype "passive"))
      (node (ref "C14") (pin "1") (pinfunction "1_1") (pintype "passive"))
      (node (ref "C15") (pin "1") (pinfunction "1_1") (pintype "passive"))
      (node (ref "C2") (pin "1") (pinfunction "1_1") (pintype "passive"))
      (node (ref "C3") (pin "1") (pinfunction "1_1") (pintype "passive"))
      (node (ref "C32") (pin "1") (pinfunction "1_1") (pintype "passive"))
      (node (ref "C4") (pin "1") (pinfunction "1_1") (pintype "passive"))
      (node (ref "C7") (pin "1") (pinfunction "1_1") (pintype "passive"))
      (node (ref "Cewka") (pin "2") (pinfunction "2_2") (pintype "passive"))
      (node (ref "J3") (pin "1") (pinfunction "1_1") (pintype "passive"))
      (node (ref "J4") (pin "1") (pinfunction "1_1") (pintype "passive"))
      (node (ref "JP1") (pin "1") (pinfunction "1_1") (pintype "passive"))
      (node (ref "LED2") (pin "2") (pinfunction "A_2") (pintype "passive"))
      (node (ref "LED3") (pin "2") (pinfunction "A_2") (pintype "passive"))
      (node (ref "LED4") (pin "2") (pinfunction "A_2") (pintype "passive"))
      (node (ref "LED5") (pin "2") (pinfunction "A_2") (pintype "passive"))
      (node (ref "LED6") (pin "2") (pinfunction "A_2") (pintype "passive"))
      (node (ref "LED7") (pin "2") (pinfunction "A_2") (pintype "passive"))
      (node (ref "LED8") (pin "2") (pinfunction "A_2") (pintype "passive"))
      (node (ref "LED9") (pin "2") (pinfunction "A_2") (pintype "passive"))
      (node (ref "Q0") (pin "1") (pinfunction "VBAT_1") (pintype "passive"))
      (node (ref "Q0") (pin "19") (pinfunction "VDD_4_19") (pintype "passive"))
      (node (ref "Q0") (pin "32") (pinfunction "VDD_2_32") (pintype "passive"))
      (node (ref "Q0") (pin "48") (pinfunction "VDD_3_48") (pintype "passive"))
      (node (ref "Q0") (pin "64") (pinfunction "VDD_1_64") (pintype "passive"))
      (node (ref "Q2") (pin "3") (pinfunction "3V3_3") (pintype "passive"))
      (node (ref "Q8") (pin "OUT") (pinfunction "OUT_OUT") (pintype "passive"))
      (node (ref "R3") (pin "2") (pinfunction "2_2") (pintype "passive"))
    )
    (net (code "86") (name "unconnected-(Q0-PA15-Pad50)") (class "Default")
      (node (ref "Q0") (pin "50") (pinfunction "PA15_50") (pintype "passive"))
    )
    (net (code "87") (name "unconnected-(Q0-PB0-Pad26)") (class "Default")
      (node (ref "Q0") (pin "26") (pinfunction "PB0_26") (pintype "passive"))
    )
    (net (code "88") (name "unconnected-(Q0-PB1-Pad27)") (class "Default")
      (node (ref "Q0") (pin "27") (pinfunction "PB1_27") (pintype "passive"))
    )
    (net (code "89") (name "unconnected-(Q0-PB13-Pad34)") (class "Default")
      (node (ref "Q0") (pin "34") (pinfunction "PB13_34") (pintype "passive"))
    )
    (net (code "90") (name "unconnected-(Q0-PB14-Pad35)") (class "Default")
      (node (ref "Q0") (pin "35") (pinfunction "PB14_35") (pintype "passive"))
    )
    (net (code "91") (name "unconnected-(Q0-PB15-Pad36)") (class "Default")
      (node (ref "Q0") (pin "36") (pinfunction "PB15_36") (pintype "passive"))
    )
    (net (code "92") (name "unconnected-(Q0-PC3-Pad11)") (class "Default")
      (node (ref "Q0") (pin "11") (pinfunction "PC3_11") (pintype "passive"))
    )
    (net (code "93") (name "unconnected-(Q0-PC10-Pad51)") (class "Default")
      (node (ref "Q0") (pin "51") (pinfunction "PC10_51") (pintype "passive"))
    )
    (net (code "94") (name "unconnected-(Q0-PC11-Pad52)") (class "Default")
      (node (ref "Q0") (pin "52") (pinfunction "PC11_52") (pintype "passive"))
    )
    (net (code "95") (name "unconnected-(Q0-PC12-Pad53)") (class "Default")
      (node (ref "Q0") (pin "53") (pinfunction "PC12_53") (pintype "passive"))
    )
    (net (code "96") (name "unconnected-(Q0-PC13-Pad2)") (class "Default")
      (node (ref "Q0") (pin "2") (pinfunction "PC13_2") (pintype "passive"))
    )
    (net (code "97") (name "unconnected-(Q0-PC14{slash}OSC32_IN-Pad3)") (class "Default")
      (node (ref "Q0") (pin "3") (pinfunction "PC14/OSC32_IN_3") (pintype "passive"))
    )
    (net (code "98") (name "unconnected-(Q0-PC15{slash}OSC32_OUT-Pad4)") (class "Default")
      (node (ref "Q0") (pin "4") (pinfunction "PC15/OSC32_OUT_4") (pintype "passive"))
    )
    (net (code "99") (name "unconnected-(Q0-PD2-Pad54)") (class "Default")
      (node (ref "Q0") (pin "54") (pinfunction "PD2_54") (pintype "passive"))
    )
    (net (code "100") (name "unconnected-(Q0-PF4-Pad18)") (class "Default")
      (node (ref "Q0") (pin "18") (pinfunction "PF4_18") (pintype "passive"))
    )
    (net (code "101") (name "unconnected-(S1-Pad3)") (class "Default")
      (node (ref "S1") (pin "3") (pintype "passive"))
    )
    (net (code "102") (name "unconnected-(S2-Pad1)") (class "Default")
      (node (ref "S2") (pin "1") (pintype "passive"))
    )
    (net (code "103") (name "unconnected-(S3-Pad1)") (class "Default")
      (node (ref "S3") (pin "1") (pintype "passive"))
    )
  )
)
